# PowerSupply.net
KiCad netlist of a schematic drawn in Altium Designer
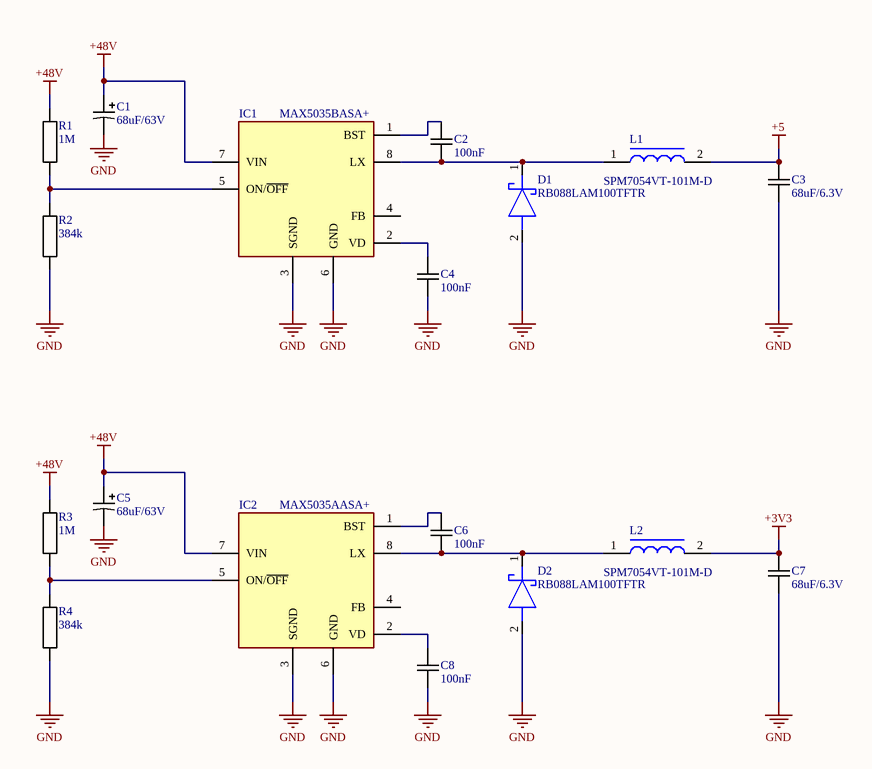
[diagram p0: PowerSupply.SchDoc]

(export (version "E")
  (design (tool "Eeschema 10.0.6"))
  (components
    (comp (ref "C1")
      (value "68uF/63V")
      (footprint "Capacitor POL SMD D10.0 H10.0")
      (description "Capacitor polarized")
      (libsource (lib "Capacitor") (part "Capacitor Polarized"))
    )
    (comp (ref "C2")
      (value "100nF")
      (footprint "CAPACITOR 1608 REFLOW")
      (description "Capacitor")
      (libsource (lib "Capacitor") (part "Capacitor"))
    )
    (comp (ref "C3")
      (value "68uF/6.3V")
      (footprint "CAPACITOR 2012 REFLOW")
      (description "Capacitor")
      (libsource (lib "Capacitor") (part "Capacitor"))
    )
    (comp (ref "C4")
      (value "100nF")
      (footprint "CAPACITOR 1608 REFLOW")
      (description "Capacitor")
      (libsource (lib "Capacitor") (part "Capacitor"))
    )
    (comp (ref "C5")
      (value "68uF/63V")
      (footprint "Capacitor POL SMD D10.0 H10.0")
      (description "Capacitor polarized")
      (libsource (lib "Capacitor") (part "Capacitor Polarized"))
    )
    (comp (ref "C6")
      (value "100nF")
      (footprint "CAPACITOR 1608 REFLOW")
      (description "Capacitor")
      (libsource (lib "Capacitor") (part "Capacitor"))
    )
    (comp (ref "C7")
      (value "68uF/6.3V")
      (footprint "CAPACITOR 2012 REFLOW")
      (description "Capacitor")
      (libsource (lib "Capacitor") (part "Capacitor"))
    )
    (comp (ref "C8")
      (value "100nF")
      (footprint "CAPACITOR 1608 REFLOW")
      (description "Capacitor")
      (libsource (lib "Capacitor") (part "Capacitor"))
    )
    (comp (ref "D1")
      (value "RB088LAM100TFTR")
      (footprint "SODFL4725X105N")
      (description "Schottky Diode")
      (fields (field (name "MOUSER PART NUMBER") "755-RB088LAM100TFTR"))
      (libsource (lib "SamacSys") (part "RB088LAM100TFTR"))
    )
    (comp (ref "D2")
      (value "RB088LAM100TFTR")
      (footprint "SODFL4725X105N")
      (description "Schottky Diode")
      (fields (field (name "MOUSER PART NUMBER") "755-RB088LAM100TFTR"))
      (libsource (lib "SamacSys") (part "RB088LAM100TFTR"))
    )
    (comp (ref "IC1")
      (value "MAX5035BASA+")
      (footprint "SOIC127P600X175-8N")
      (description "Integrated Circuit")
      (fields (field (name "MOUSER PART NUMBER") "700-MAX5035BASA"))
      (libsource (lib "SamacSys") (part "MAX5035BASA+"))
    )
    (comp (ref "IC2")
      (value "MAX5035AASA+")
      (footprint "SOIC127P600X175-8N")
      (description "Integrated Circuit")
      (fields
        (field (name "MANUFACTURER_PART_NUMBER") "MAX5035BASA+")
        (field (name "MOUSER PART NUMBER") "700-MAX5035BASA")
      )
      (libsource (lib "SamacSys") (part "MAX5035BASA+"))
    )
    (comp (ref "L1")
      (value "SPM7054VT-101M-D")
      (footprint "SPM7054VT")
      (description "Inductor (FeSi Core)")
      (fields (field (name "MOUSER PART NUMBER") "810-SPM7054VT-101M-D"))
      (libsource (lib "SamacSys") (part "SPM7054VT-101M-D"))
    )
    (comp (ref "L2")
      (value "SPM7054VT-101M-D")
      (footprint "SPM7054VT")
      (description "Inductor (FeSi Core)")
      (fields (field (name "MOUSER PART NUMBER") "810-SPM7054VT-101M-D"))
      (libsource (lib "SamacSys") (part "SPM7054VT-101M-D"))
    )
    (comp (ref "R1")
      (value "1M")
      (footprint "RESISTOR 1608 REFLOW")
      (description "Resistor")
      (libsource (lib "Resistor") (part "Resistor"))
    )
    (comp (ref "R2")
      (value "384k")
      (footprint "RESISTOR 1608 REFLOW")
      (description "Resistor")
      (libsource (lib "Resistor") (part "Resistor"))
    )
    (comp (ref "R3")
      (value "1M")
      (footprint "RESISTOR 1608 REFLOW")
      (description "Resistor")
      (libsource (lib "Resistor") (part "Resistor"))
    )
    (comp (ref "R4")
      (value "384k")
      (footprint "RESISTOR 1608 REFLOW")
      (description "Resistor")
      (libsource (lib "Resistor") (part "Resistor"))
    )
  )
  (nets
    (net (code "1") (name "+3V3") (class "Default")
      (node (ref "C7") (pin "2") (pinfunction "2_2") (pintype "passive"))
      (node (ref "L2") (pin "2") (pinfunction "2_2") (pintype "passive"))
    )
    (net (code "2") (name "+5") (class "Default")
      (node (ref "C3") (pin "2") (pinfunction "2_2") (pintype "passive"))
      (node (ref "L1") (pin "2") (pinfunction "2_2") (pintype "passive"))
    )
    (net (code "3") (name "+48V") (class "Default")
      (node (ref "C1") (pin "1") (pinfunction "1_1") (pintype "passive"))
      (node (ref "C5") (pin "1") (pinfunction "1_1") (pintype "passive"))
      (node (ref "IC1") (pin "7") (pinfunction "VIN_7") (pintype "passive"))
      (node (ref "IC2") (pin "7") (pinfunction "VIN_7") (pintype "passive"))
      (node (ref "R1") (pin "2") (pinfunction "2_2") (pintype "passive"))
      (node (ref "R3") (pin "2") (pinfunction "2_2") (pintype "passive"))
    )
    (net (code "4") (name "GND") (class "Default")
      (node (ref "C1") (pin "2") (pinfunction "2_2") (pintype "passive"))
      (node (ref "C3") (pin "1") (pinfunction "1_1") (pintype "passive"))
      (node (ref "C4") (pin "2") (pinfunction "2_2") (pintype "passive"))
      (node (ref "C5") (pin "2") (pinfunction "2_2") (pintype "passive"))
      (node (ref "C7") (pin "1") (pinfunction "1_1") (pintype "passive"))
      (node (ref "C8") (pin "2") (pinfunction "2_2") (pintype "passive"))
      (node (ref "D1") (pin "2") (pinfunction "A_2") (pintype "passive"))
      (node (ref "D2") (pin "2") (pinfunction "A_2") (pintype "passive"))
      (node (ref "IC1") (pin "3") (pinfunction "SGND_3") (pintype "passive"))
      (node (ref "IC1") (pin "6") (pinfunction "GND_6") (pintype "passive"))
      (node (ref "IC2") (pin "3") (pinfunction "SGND_3") (pintype "passive"))
      (node (ref "IC2") (pin "6") (pinfunction "GND_6") (pintype "passive"))
      (node (ref "R2") (pin "1") (pinfunction "1_1") (pintype "passive"))
      (node (ref "R4") (pin "1") (pinfunction "1_1") (pintype "passive"))
    )
    (net (code "5") (name "Net-(D1-K)") (class "Default")
      (node (ref "C2") (pin "2") (pinfunction "2_2") (pintype "passive"))
      (node (ref "D1") (pin "1") (pinfunction "K_1") (pintype "passive"))
      (node (ref "IC1") (pin "8") (pinfunction "LX_8") (pintype "passive"))
      (node (ref "L1") (pin "1") (pinfunction "1_1") (pintype "passive"))
    )
    (net (code "6") (name "Net-(D2-K)") (class "Default")
      (node (ref "C6") (pin "2") (pinfunction "2_2") (pintype "passive"))
      (node (ref "D2") (pin "1") (pinfunction "K_1") (pintype "passive"))
      (node (ref "IC2") (pin "8") (pinfunction "LX_8") (pintype "passive"))
      (node (ref "L2") (pin "1") (pinfunction "1_1") (pintype "passive"))
    )
    (net (code "7") (name "Net-(IC1-BST)") (class "Default")
      (node (ref "C2") (pin "1") (pinfunction "1_1") (pintype "passive"))
      (node (ref "IC1") (pin "1") (pinfunction "BST_1") (pintype "passive"))
    )
    (net (code "8") (name "Net-(IC1-ON{slash}~{OFF})") (class "Default")
      (node (ref "IC1") (pin "5") (pinfunction "ON/~{OFF}_5") (pintype "passive"))
      (node (ref "R1") (pin "1") (pinfunction "1_1") (pintype "passive"))
      (node (ref "R2") (pin "2") (pinfunction "2_2") (pintype "passive"))
    )
    (net (code "9") (name "Net-(IC1-VD)") (class "Default")
      (node (ref "C4") (pin "1") (pinfunction "1_1") (pintype "passive"))
      (node (ref "IC1") (pin "2") (pinfunction "VD_2") (pintype "passive"))
    )
    (net (code "10") (name "Net-(IC2-BST)") (class "Default")
      (node (ref "C6") (pin "1") (pinfunction "1_1") (pintype "passive"))
      (node (ref "IC2") (pin "1") (pinfunction "BST_1") (pintype "passive"))
    )
    (net (code "11") (name "Net-(IC2-ON{slash}~{OFF})") (class "Default")
      (node (ref "IC2") (pin "5") (pinfunction "ON/~{OFF}_5") (pintype "passive"))
      (node (ref "R3") (pin "1") (pinfunction "1_1") (pintype "passive"))
      (node (ref "R4") (pin "2") (pinfunction "2_2") (pintype "passive"))
    )
    (net (code "12") (name "Net-(IC2-VD)") (class "Default")
      (node (ref "C8") (pin "1") (pinfunction "1_1") (pintype "passive"))
      (node (ref "IC2") (pin "2") (pinfunction "VD_2") (pintype "passive"))
    )
    (net (code "13") (name "unconnected-(IC1-FB-Pad4)") (class "Default")
      (node (ref "IC1") (pin "4") (pinfunction "FB_4") (pintype "passive"))
    )
    (net (code "14") (name "unconnected-(IC2-FB-Pad4)") (class "Default")
      (node (ref "IC2") (pin "4") (pinfunction "FB_4") (pintype "passive"))
    )
  )
)
